# FTD232rl_breakout.net
KiCad netlist of a schematic drawn in EAGLE
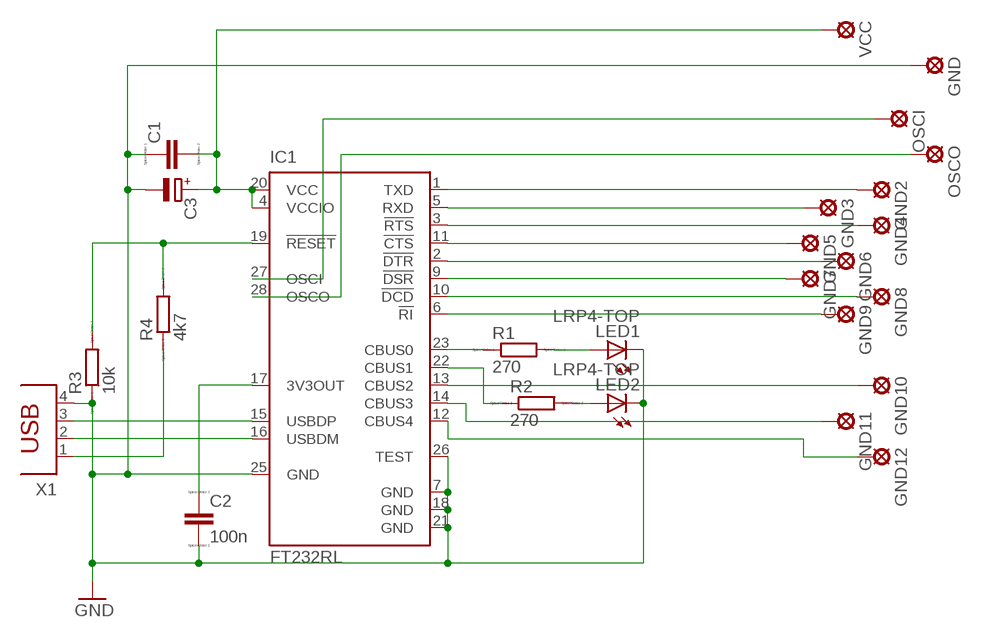
[diagram p0: schematic, sheet 1]

(export (version "E")
  (design (tool "Eeschema 10.0.6"))
  (components
    (comp (ref "C1")
      (value "C-EUC0603K")
      (footprint "eagle-import:C0603K")
      (libsource (lib "eagle-import") (part "C-EUC0603K"))
    )
    (comp (ref "C2")
      (value "100n")
      (footprint "eagle-import:C0603K")
      (libsource (lib "eagle-import") (part "C-EUC0603K"))
    )
    (comp (ref "C3")
      (value "CPOL-EU153CLV-0505")
      (footprint "eagle-import:153CLV-0505")
      (libsource (lib "eagle-import") (part "CPOL-EU153CLV-0505"))
    )
    (comp (ref "GND")
      (value "LSP10")
      (footprint "eagle-import:LSP10")
      (libsource (lib "eagle-import") (part "LSP10"))
    )
    (comp (ref "GND2")
      (value "LSP10")
      (footprint "eagle-import:LSP10")
      (libsource (lib "eagle-import") (part "LSP10"))
    )
    (comp (ref "GND3")
      (value "LSP10")
      (footprint "eagle-import:LSP10")
      (libsource (lib "eagle-import") (part "LSP10"))
    )
    (comp (ref "GND4")
      (value "LSP10")
      (footprint "eagle-import:LSP10")
      (libsource (lib "eagle-import") (part "LSP10"))
    )
    (comp (ref "GND5")
      (value "LSP10")
      (footprint "eagle-import:LSP10")
      (libsource (lib "eagle-import") (part "LSP10"))
    )
    (comp (ref "GND6")
      (value "LSP10")
      (footprint "eagle-import:LSP10")
      (libsource (lib "eagle-import") (part "LSP10"))
    )
    (comp (ref "GND7")
      (value "LSP10")
      (footprint "eagle-import:LSP10")
      (libsource (lib "eagle-import") (part "LSP10"))
    )
    (comp (ref "GND8")
      (value "LSP10")
      (footprint "eagle-import:LSP10")
      (libsource (lib "eagle-import") (part "LSP10"))
    )
    (comp (ref "GND9")
      (value "LSP10")
      (footprint "eagle-import:LSP10")
      (libsource (lib "eagle-import") (part "LSP10"))
    )
    (comp (ref "GND10")
      (value "LSP10")
      (footprint "eagle-import:LSP10")
      (libsource (lib "eagle-import") (part "LSP10"))
    )
    (comp (ref "GND11")
      (value "LSP10")
      (footprint "eagle-import:LSP10")
      (libsource (lib "eagle-import") (part "LSP10"))
    )
    (comp (ref "GND12")
      (value "LSP10")
      (footprint "eagle-import:LSP10")
      (libsource (lib "eagle-import") (part "LSP10"))
    )
    (comp (ref "IC1")
      (value "FT232RL")
      (footprint "eagle-import:SSOP28")
      (libsource (lib "eagle-import") (part "FT232RL"))
    )
    (comp (ref "LED1")
      (value "LRP4-TOP")
      (footprint "eagle-import:P47F-TOP")
      (libsource (lib "eagle-import") (part "P4-TOPLR"))
    )
    (comp (ref "LED2")
      (value "LRP4-TOP")
      (footprint "eagle-import:P47F-TOP")
      (libsource (lib "eagle-import") (part "P4-TOPLR"))
    )
    (comp (ref "OSCI")
      (value "LSP10")
      (footprint "eagle-import:LSP10")
      (libsource (lib "eagle-import") (part "LSP10"))
    )
    (comp (ref "OSCO")
      (value "LSP10")
      (footprint "eagle-import:LSP10")
      (libsource (lib "eagle-import") (part "LSP10"))
    )
    (comp (ref "R1")
      (value "270")
      (footprint "eagle-import:0207_10")
      (fields (field (name "SPICEPREFIX") "270"))
      (libsource (lib "eagle-import") (part "R-EU_0207_10"))
    )
    (comp (ref "R2")
      (value "270")
      (footprint "eagle-import:0207_10")
      (libsource (lib "eagle-import") (part "R-EU_0207_10"))
    )
    (comp (ref "R3")
      (value "10k")
      (footprint "eagle-import:0207_10")
      (fields (field (name "SPICEPREFIX") "270"))
      (libsource (lib "eagle-import") (part "R-EU_0207_10"))
    )
    (comp (ref "R4")
      (value "4k7")
      (footprint "eagle-import:0207_10")
      (fields (field (name "SPICEPREFIX") "270"))
      (libsource (lib "eagle-import") (part "R-EU_0207_10"))
    )
    (comp (ref "VCC")
      (value "LSP10")
      (footprint "eagle-import:LSP10")
      (libsource (lib "eagle-import") (part "LSP10"))
    )
    (comp (ref "X1")
      (value "PN87520")
      (footprint "eagle-import:PN87520")
      (libsource (lib "eagle-import") (part "PN87520"))
    )
  )
  (nets
    (net (code "1") (name "GND") (class "Default")
      (node (ref "C1") (pin "1") (pinfunction "1_1") (pintype "passive"))
      (node (ref "C2") (pin "2") (pinfunction "2_2") (pintype "passive"))
      (node (ref "C3") (pin "-") (pinfunction "-_-") (pintype "passive"))
      (node (ref "GND") (pin "MP") (pinfunction "MP_MP") (pintype "passive"))
      (node (ref "IC1") (pin "18") (pinfunction "GND_18") (pintype "power_in"))
      (node (ref "IC1") (pin "21") (pinfunction "GND_21") (pintype "power_in"))
      (node (ref "IC1") (pin "25") (pinfunction "GND_25") (pintype "power_in"))
      (node (ref "IC1") (pin "26") (pinfunction "TEST_26") (pintype "input"))
      (node (ref "IC1") (pin "7") (pinfunction "GND_7") (pintype "power_in"))
      (node (ref "LED1") (pin "C") (pinfunction "C_C") (pintype "passive"))
      (node (ref "LED2") (pin "C") (pinfunction "C_C") (pintype "passive"))
      (node (ref "R3") (pin "1") (pinfunction "1_1") (pintype "passive"))
      (node (ref "X1") (pin "4") (pinfunction "4_4") (pintype "passive"))
    )
    (net (code "2") (name "Net-(IC1-3V3OUT)") (class "Default")
      (node (ref "C2") (pin "1") (pinfunction "1_1") (pintype "passive"))
      (node (ref "IC1") (pin "17") (pinfunction "3V3OUT_17") (pintype "output"))
    )
    (net (code "3") (name "Net-(IC1-CBUS0)") (class "Default")
      (node (ref "IC1") (pin "23") (pinfunction "CBUS0_23") (pintype "bidirectional"))
      (node (ref "R1") (pin "1") (pinfunction "1_1") (pintype "passive"))
    )
    (net (code "4") (name "Net-(IC1-CBUS1)") (class "Default")
      (node (ref "IC1") (pin "22") (pinfunction "CBUS1_22") (pintype "bidirectional"))
      (node (ref "R2") (pin "1") (pinfunction "1_1") (pintype "passive"))
    )
    (net (code "5") (name "Net-(IC1-CBUS2)") (class "Default")
      (node (ref "GND10") (pin "MP") (pinfunction "MP_MP") (pintype "passive"))
      (node (ref "IC1") (pin "13") (pinfunction "CBUS2_13") (pintype "bidirectional"))
    )
    (net (code "6") (name "Net-(IC1-CBUS3)") (class "Default")
      (node (ref "GND11") (pin "MP") (pinfunction "MP_MP") (pintype "passive"))
      (node (ref "IC1") (pin "14") (pinfunction "CBUS3_14") (pintype "bidirectional"))
    )
    (net (code "7") (name "Net-(IC1-CBUS4)") (class "Default")
      (node (ref "GND12") (pin "MP") (pinfunction "MP_MP") (pintype "passive"))
      (node (ref "IC1") (pin "12") (pinfunction "CBUS4_12") (pintype "bidirectional"))
    )
    (net (code "8") (name "Net-(IC1-OSCI)") (class "Default")
      (node (ref "IC1") (pin "27") (pinfunction "OSCI_27") (pintype "input"))
      (node (ref "OSCI") (pin "MP") (pinfunction "MP_MP") (pintype "passive"))
    )
    (net (code "9") (name "Net-(IC1-OSCO)") (class "Default")
      (node (ref "IC1") (pin "28") (pinfunction "OSCO_28") (pintype "output"))
      (node (ref "OSCO") (pin "MP") (pinfunction "MP_MP") (pintype "passive"))
    )
    (net (code "10") (name "Net-(IC1-RXD)") (class "Default")
      (node (ref "GND3") (pin "MP") (pinfunction "MP_MP") (pintype "passive"))
      (node (ref "IC1") (pin "5") (pinfunction "RXD_5") (pintype "input"))
    )
    (net (code "11") (name "Net-(IC1-TXD)") (class "Default")
      (node (ref "GND2") (pin "MP") (pinfunction "MP_MP") (pintype "passive"))
      (node (ref "IC1") (pin "1") (pinfunction "TXD_1") (pintype "output"))
    )
    (net (code "12") (name "Net-(IC1-USBDM)") (class "Default")
      (node (ref "IC1") (pin "16") (pinfunction "USBDM_16") (pintype "bidirectional"))
      (node (ref "X1") (pin "2") (pinfunction "2_2") (pintype "passive"))
    )
    (net (code "13") (name "Net-(IC1-USBDP)") (class "Default")
      (node (ref "IC1") (pin "15") (pinfunction "USBDP_15") (pintype "bidirectional"))
      (node (ref "X1") (pin "3") (pinfunction "3_3") (pintype "passive"))
    )
    (net (code "14") (name "Net-(IC1-VCC)") (class "Default")
      (node (ref "C1") (pin "2") (pinfunction "2_2") (pintype "passive"))
      (node (ref "C3") (pin "+") (pinfunction "+_+") (pintype "passive"))
      (node (ref "IC1") (pin "20") (pinfunction "VCC_20") (pintype "power_in"))
      (node (ref "IC1") (pin "4") (pinfunction "VCCIO_4") (pintype "power_in"))
      (node (ref "VCC") (pin "MP") (pinfunction "MP_MP") (pintype "passive"))
    )
    (net (code "15") (name "Net-(IC1-~{CTS})") (class "Default")
      (node (ref "GND5") (pin "MP") (pinfunction "MP_MP") (pintype "passive"))
      (node (ref "IC1") (pin "11") (pinfunction "~{CTS}_11") (pintype "input"))
    )
    (net (code "16") (name "Net-(IC1-~{DCD})") (class "Default")
      (node (ref "GND8") (pin "MP") (pinfunction "MP_MP") (pintype "passive"))
      (node (ref "IC1") (pin "10") (pinfunction "~{DCD}_10") (pintype "input"))
    )
    (net (code "17") (name "Net-(IC1-~{DSR})") (class "Default")
      (node (ref "GND7") (pin "MP") (pinfunction "MP_MP") (pintype "passive"))
      (node (ref "IC1") (pin "9") (pinfunction "~{DSR}_9") (pintype "input"))
    )
    (net (code "18") (name "Net-(IC1-~{DTR})") (class "Default")
      (node (ref "GND6") (pin "MP") (pinfunction "MP_MP") (pintype "passive"))
      (node (ref "IC1") (pin "2") (pinfunction "~{DTR}_2") (pintype "output"))
    )
    (net (code "19") (name "Net-(IC1-~{RESET})") (class "Default")
      (node (ref "IC1") (pin "19") (pinfunction "~{RESET}_19") (pintype "input"))
      (node (ref "R3") (pin "2") (pinfunction "2_2") (pintype "passive"))
      (node (ref "R4") (pin "2") (pinfunction "2_2") (pintype "passive"))
    )
    (net (code "20") (name "Net-(IC1-~{RI})") (class "Default")
      (node (ref "GND9") (pin "MP") (pinfunction "MP_MP") (pintype "passive"))
      (node (ref "IC1") (pin "6") (pinfunction "~{RI}_6") (pintype "input"))
    )
    (net (code "21") (name "Net-(IC1-~{RTS})") (class "Default")
      (node (ref "GND4") (pin "MP") (pinfunction "MP_MP") (pintype "passive"))
      (node (ref "IC1") (pin "3") (pinfunction "~{RTS}_3") (pintype "output"))
    )
    (net (code "22") (name "Net-(LED1-PadA)") (class "Default")
      (node (ref "LED1") (pin "A") (pinfunction "A_A") (pintype "passive"))
      (node (ref "R1") (pin "2") (pinfunction "2_2") (pintype "passive"))
    )
    (net (code "23") (name "Net-(LED2-PadA)") (class "Default")
      (node (ref "LED2") (pin "A") (pinfunction "A_A") (pintype "passive"))
      (node (ref "R2") (pin "2") (pinfunction "2_2") (pintype "passive"))
    )
    (net (code "24") (name "Net-(R4-Pad1)") (class "Default")
      (node (ref "R4") (pin "1") (pinfunction "1_1") (pintype "passive"))
      (node (ref "X1") (pin "1") (pinfunction "1_1") (pintype "passive"))
    )
  )
)
